# p_injector.net
KiCad netlist of a schematic drawn in EAGLE
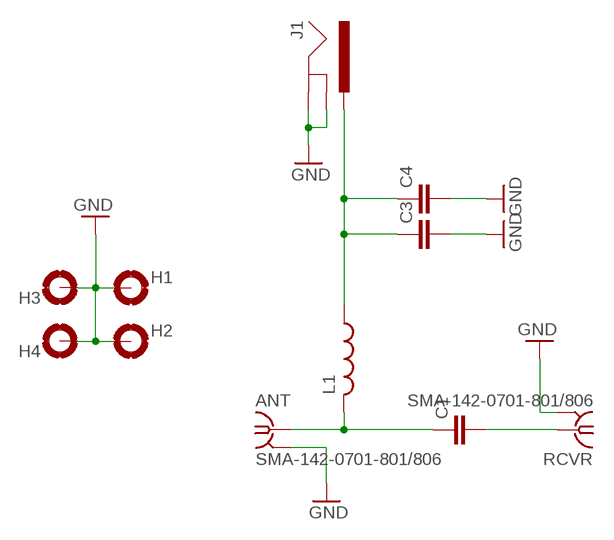
[diagram p0: schematic, sheet 1]

(export (version "E")
  (design (tool "Eeschema 10.0.6"))
  (components
    (comp (ref "ANT")
      (value "SMA-142-0701-801/806")
      (footprint "eagle-import:J502-ND-142-0701-801_806")
      (fields (field (name "MF") "JOHNSON COMPONENTS") (field (name "MPN") "142-0701-801"))
      (libsource (lib "eagle-import") (part "SMA-142-0701-801/806"))
    )
    (comp (ref "C1")
      (value "C_0805_PTH")
      (footprint "eagle-import:C0805K")
      (libsource (lib "eagle-import") (part "C_0805_PTH"))
    )
    (comp (ref "C3")
      (value "C_0805_SMD")
      (footprint "eagle-import:C0805")
      (libsource (lib "eagle-import") (part "C_0805_SMD"))
    )
    (comp (ref "C4")
      (value "C_0805_SMD")
      (footprint "eagle-import:C0805")
      (libsource (lib "eagle-import") (part "C_0805_SMD"))
    )
    (comp (ref "H1")
      (value "MOUNT-PAD-ROUND3.0")
      (footprint "eagle-import:3,0-PAD")
      (libsource (lib "eagle-import") (part "MOUNT-PAD-ROUND3.0"))
    )
    (comp (ref "H2")
      (value "MOUNT-PAD-ROUND3.0")
      (footprint "eagle-import:3,0-PAD")
      (libsource (lib "eagle-import") (part "MOUNT-PAD-ROUND3.0"))
    )
    (comp (ref "H3")
      (value "MOUNT-PAD-ROUND3.0")
      (footprint "eagle-import:3,0-PAD")
      (libsource (lib "eagle-import") (part "MOUNT-PAD-ROUND3.0"))
    )
    (comp (ref "H4")
      (value "MOUNT-PAD-ROUND3.0")
      (footprint "eagle-import:3,0-PAD")
      (libsource (lib "eagle-import") (part "MOUNT-PAD-ROUND3.0"))
    )
    (comp (ref "J1")
      (value "POWER_JACKPOWER_JACK_SLOT")
      (footprint "eagle-import:POWER_JACK_PTH_SLOT")
      (libsource (lib "eagle-import") (part "POWER_JACKPOWER_JACK_SLOT"))
    )
    (comp (ref "L1")
      (value "L_0805_PTH")
      (footprint "eagle-import:M0805")
      (libsource (lib "eagle-import") (part "L_0805_PTH"))
    )
    (comp (ref "RCVR")
      (value "SMA-142-0701-801/806")
      (footprint "eagle-import:J502-ND-142-0701-801_806")
      (fields (field (name "MF") "JOHNSON COMPONENTS") (field (name "MPN") "142-0701-801"))
      (libsource (lib "eagle-import") (part "SMA-142-0701-801/806"))
    )
  )
  (nets
    (net (code "1") (name "GND") (class "Default")
      (node (ref "ANT") (pin "G@1") (pinfunction "2_G@1") (pintype "passive"))
      (node (ref "ANT") (pin "G@2") (pinfunction "2_G@2") (pintype "passive"))
      (node (ref "ANT") (pin "G@3") (pinfunction "2_G@3") (pintype "passive"))
      (node (ref "ANT") (pin "G@4") (pinfunction "2_G@4") (pintype "passive"))
      (node (ref "C3") (pin "2") (pinfunction "2_2") (pintype "passive"))
      (node (ref "C4") (pin "2") (pinfunction "2_2") (pintype "passive"))
      (node (ref "H1") (pin "B3,0") (pinfunction "MOUNT_B3,0") (pintype "passive"))
      (node (ref "H2") (pin "B3,0") (pinfunction "MOUNT_B3,0") (pintype "passive"))
      (node (ref "H3") (pin "B3,0") (pinfunction "MOUNT_B3,0") (pintype "passive"))
      (node (ref "H4") (pin "B3,0") (pinfunction "MOUNT_B3,0") (pintype "passive"))
      (node (ref "J1") (pin "GND") (pinfunction "GND_GND") (pintype "bidirectional"))
      (node (ref "J1") (pin "GNDBREAK") (pinfunction "GNDBREAK_GNDBREAK") (pintype "bidirectional"))
      (node (ref "RCVR") (pin "G@1") (pinfunction "2_G@1") (pintype "passive"))
      (node (ref "RCVR") (pin "G@2") (pinfunction "2_G@2") (pintype "passive"))
      (node (ref "RCVR") (pin "G@3") (pinfunction "2_G@3") (pintype "passive"))
      (node (ref "RCVR") (pin "G@4") (pinfunction "2_G@4") (pintype "passive"))
    )
    (net (code "2") (name "Net-(ANT-Pad1)") (class "Default")
      (node (ref "ANT") (pin "1") (pinfunction "1_1") (pintype "passive"))
      (node (ref "C1") (pin "1") (pinfunction "1_1") (pintype "passive"))
      (node (ref "C1") (pin "P$1") (pinfunction "1_P$1") (pintype "passive"))
      (node (ref "L1") (pin "2") (pinfunction "2_2") (pintype "passive"))
      (node (ref "L1") (pin "P$2") (pinfunction "2_P$2") (pintype "passive"))
    )
    (net (code "3") (name "Net-(C1-2-PadP$2)") (class "Default")
      (node (ref "C1") (pin "2") (pinfunction "2_2") (pintype "passive"))
      (node (ref "C1") (pin "P$2") (pinfunction "2_P$2") (pintype "passive"))
      (node (ref "RCVR") (pin "1") (pinfunction "1_1") (pintype "passive"))
    )
    (net (code "4") (name "Net-(C3-Pad1)") (class "Default")
      (node (ref "C3") (pin "1") (pinfunction "1_1") (pintype "passive"))
      (node (ref "C4") (pin "1") (pinfunction "1_1") (pintype "passive"))
      (node (ref "J1") (pin "PWR") (pinfunction "PWR_PWR") (pintype "bidirectional"))
      (node (ref "L1") (pin "1") (pinfunction "1_1") (pintype "passive"))
      (node (ref "L1") (pin "P$1") (pinfunction "1_P$1") (pintype "passive"))
    )
  )
)
